# 04_-ADDITIONAL-BOM-PARTS.net
KiCad netlist of a schematic drawn in Altium Designer
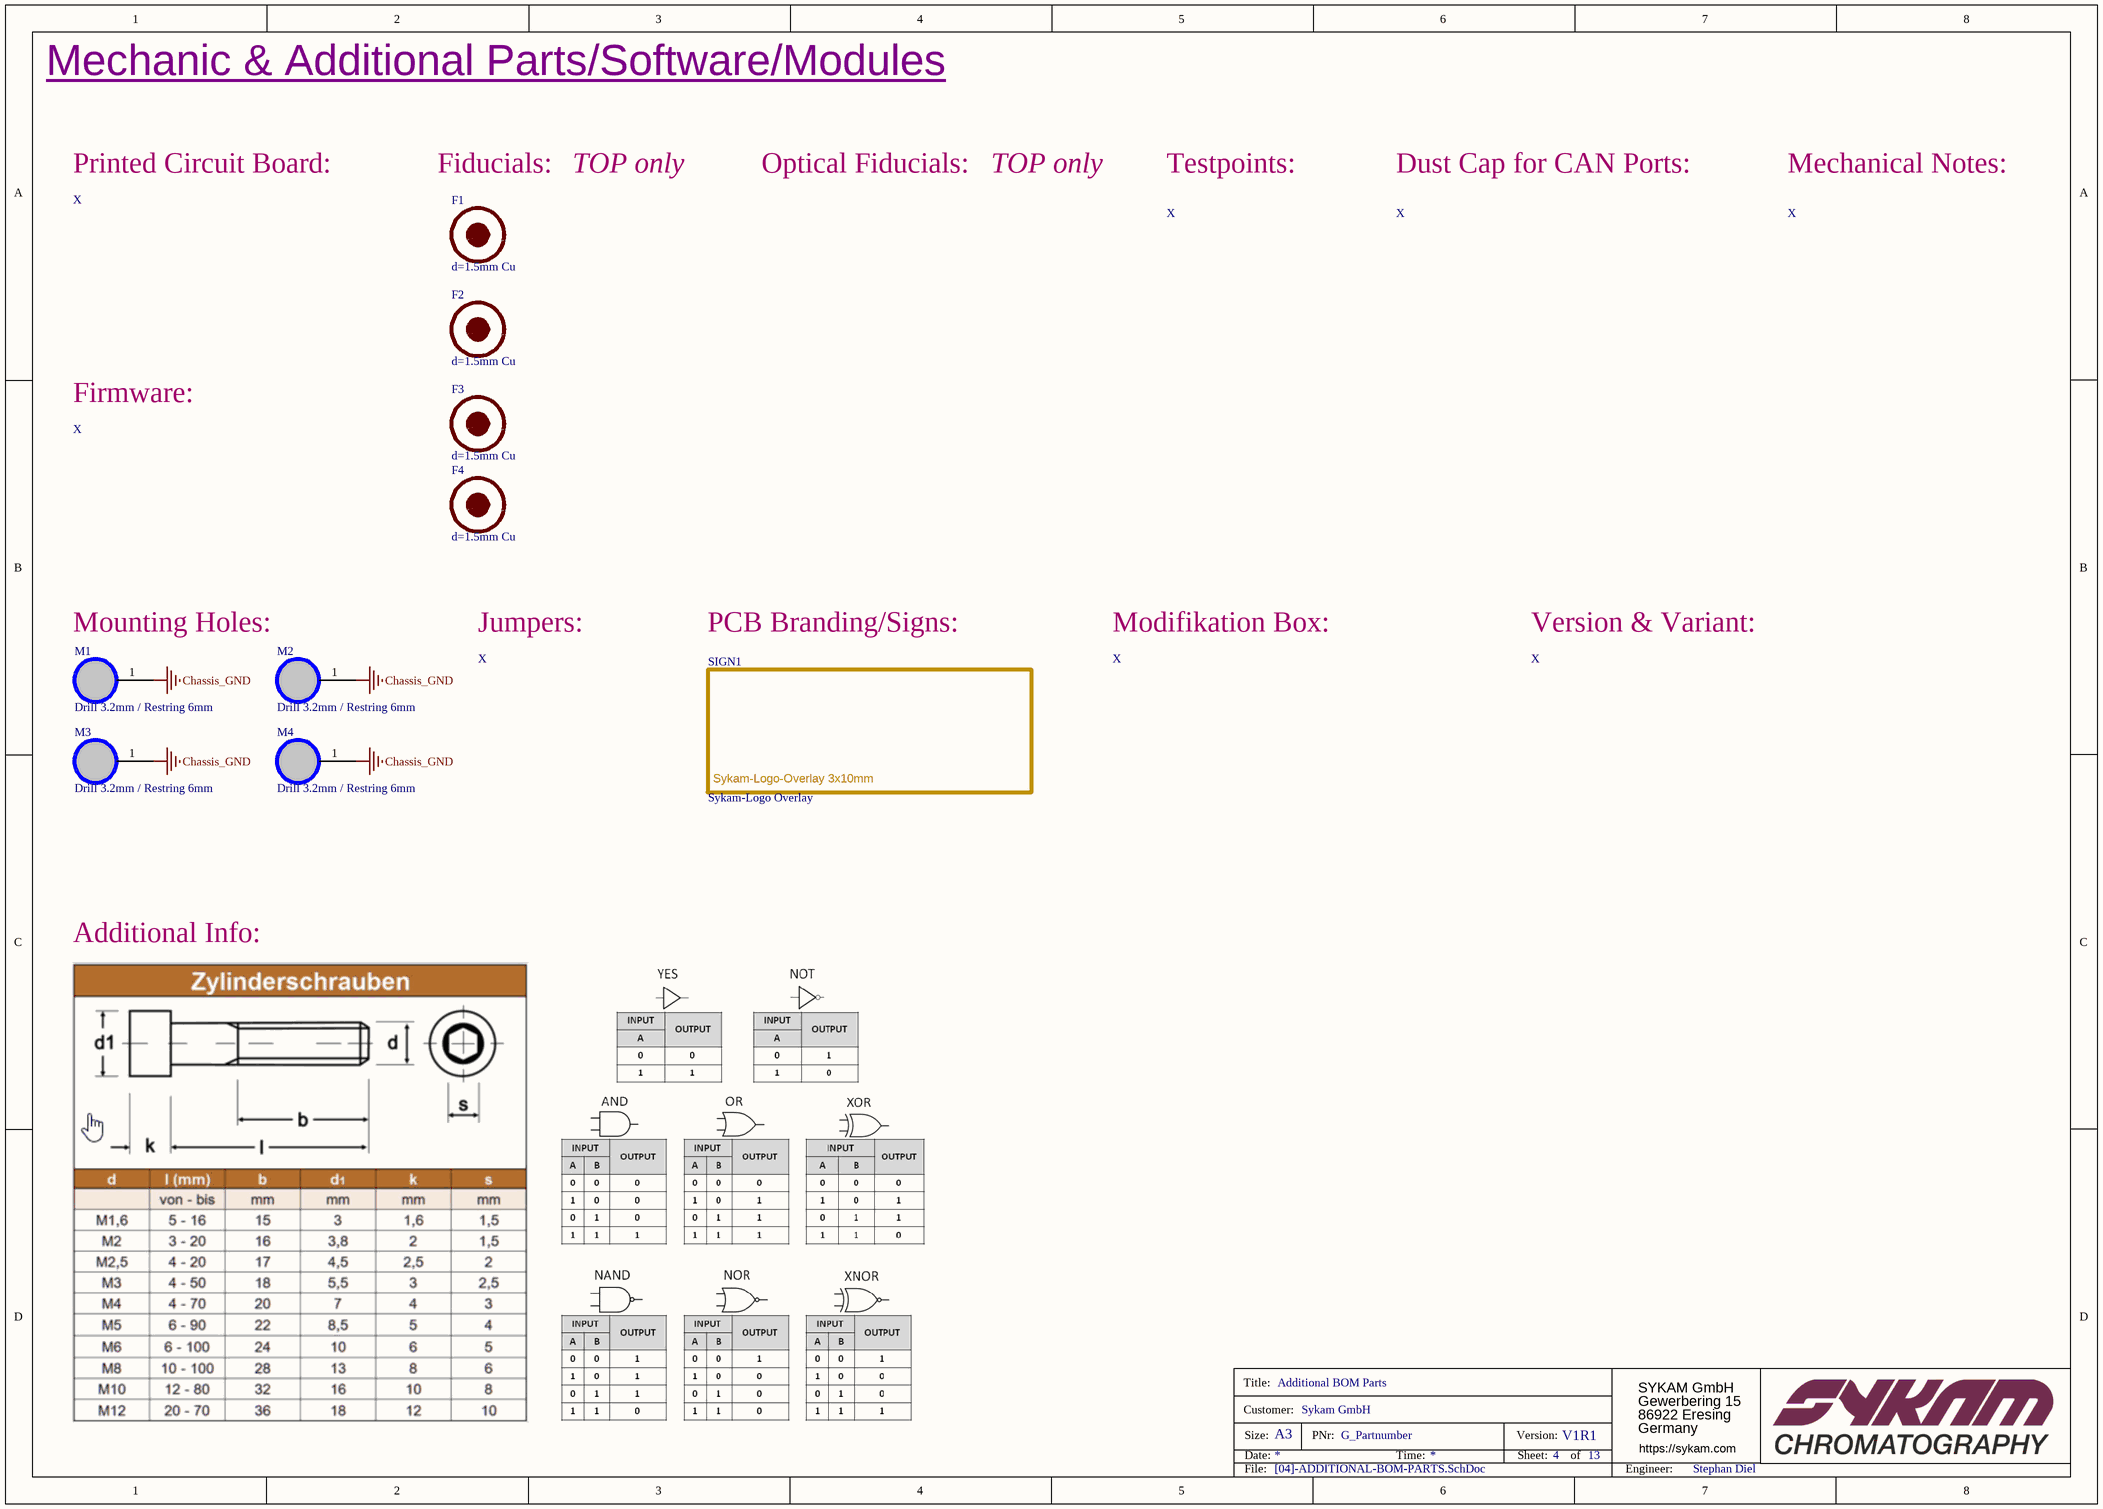
[diagram p0: [04]-ADDITIONAL-BOM-PARTS.SchDoc]

(export (version "E")
  (design (tool "Eeschema 10.0.6"))
  (components
    (comp (ref "F1")
      (value "d=1.5mm Cu")
      (footprint "Fiducial_1")
      (description "Fiducial Passermarke mit 1.5mm Druchmesser.")
      (libsource (lib "Sykam-Mech1") (part "Fiducial_1,5mm"))
    )
    (comp (ref "F2")
      (value "d=1.5mm Cu")
      (footprint "Fiducial_1")
      (description "Fiducial Passermarke mit 1.5mm Druchmesser.")
      (libsource (lib "Sykam-Mech1") (part "Fiducial_1,5mm"))
    )
    (comp (ref "F3")
      (value "d=1.5mm Cu")
      (footprint "Fiducial_1")
      (description "Fiducial Passermarke mit 1.5mm Druchmesser.")
      (libsource (lib "Sykam-Mech1") (part "Fiducial_1,5mm"))
    )
    (comp (ref "F4")
      (value "d=1.5mm Cu")
      (footprint "Fiducial_1")
      (description "Fiducial Passermarke mit 1.5mm Druchmesser.")
      (libsource (lib "Sykam-Mech1") (part "Fiducial_1,5mm"))
    )
    (comp (ref "M1")
      (value "Drill 3.2mm / Restring 6mm")
      (footprint "Mountingholes_M3_ZylKS_Plated")
      (libsource (lib "Sykam-Mech1") (part "Mountinghole_M3"))
    )
    (comp (ref "M2")
      (value "Drill 3.2mm / Restring 6mm")
      (footprint "Mountingholes_M3_ZylKS_Plated")
      (libsource (lib "Sykam-Mech1") (part "Mountinghole_M3"))
    )
    (comp (ref "M3")
      (value "Drill 3.2mm / Restring 6mm")
      (footprint "Mountingholes_M3_ZylKS_Plated")
      (libsource (lib "Sykam-Mech1") (part "Mountinghole_M3"))
    )
    (comp (ref "M4")
      (value "Drill 3.2mm / Restring 6mm")
      (footprint "Mountingholes_M3_ZylKS_Plated")
      (libsource (lib "Sykam-Mech1") (part "Mountinghole_M3"))
    )
    (comp (ref "SIGN1")
      (value "Sykam-Logo Overlay")
      (footprint "Logo-Sykam_3x10mm")
      (description "Sykam Logo im Overlay")
      (libsource (lib "Sykam-Mech1") (part "Logo-3x10mm"))
    )
  )
  (nets
    (net (code "1") (name "Chassis_GND") (class "Default")
      (node (ref "M1") (pin "1") (pinfunction "1_1") (pintype "passive"))
      (node (ref "M2") (pin "1") (pinfunction "1_1") (pintype "passive"))
      (node (ref "M3") (pin "1") (pinfunction "1_1") (pintype "passive"))
      (node (ref "M4") (pin "1") (pinfunction "1_1") (pintype "passive"))
    )
  )
)
